# power_divider.net
KiCad netlist of a schematic drawn in EAGLE
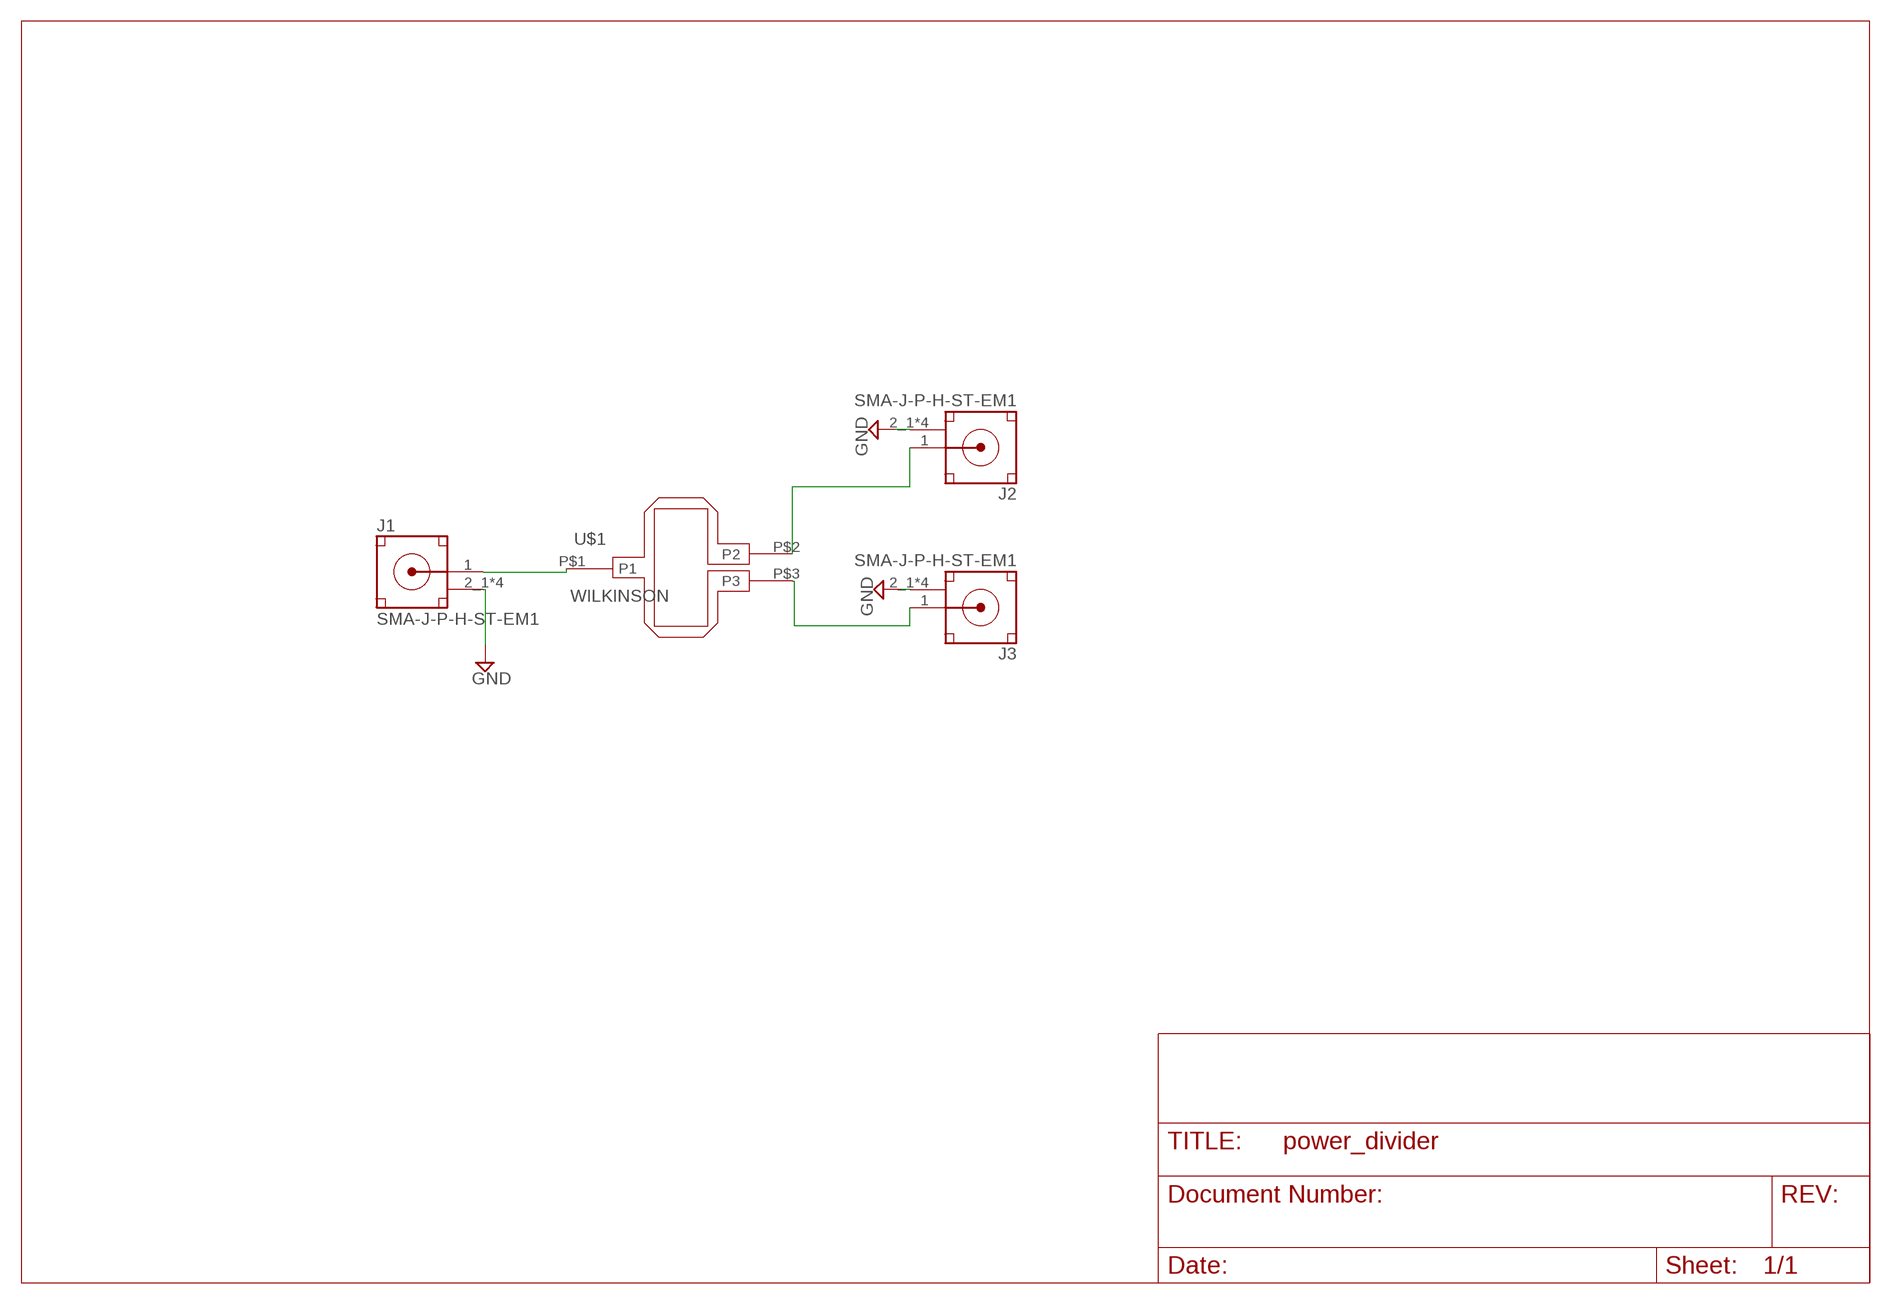
[diagram p0: schematic, sheet 1]

(export (version "E")
  (design (tool "Eeschema 10.0.6"))
  (components
    (comp (ref "J1")
      (value "SMA-J-P-H-ST-EM1")
      (footprint "eagle-import:SMA-J-P-H-ST-EM1")
      (fields (field (name "DIGI-KEY_PART_NUMBER") "SAM8857-ND") (field (name "MF") "Samtec"))
      (libsource (lib "eagle-import") (part "SMA-J-P-H-ST-EM1"))
    )
    (comp (ref "J2")
      (value "SMA-J-P-H-ST-EM1")
      (footprint "eagle-import:SMA-J-P-H-ST-EM1")
      (fields (field (name "DIGI-KEY_PART_NUMBER") "SAM8857-ND") (field (name "MF") "Samtec"))
      (libsource (lib "eagle-import") (part "SMA-J-P-H-ST-EM1"))
    )
    (comp (ref "J3")
      (value "SMA-J-P-H-ST-EM1")
      (footprint "eagle-import:SMA-J-P-H-ST-EM1")
      (fields (field (name "DIGI-KEY_PART_NUMBER") "SAM8857-ND") (field (name "MF") "Samtec"))
      (libsource (lib "eagle-import") (part "SMA-J-P-H-ST-EM1"))
    )
    (comp (ref "U$1")
      (value "WILKINSON")
      (footprint "eagle-import:WILKINSON")
      (libsource (lib "eagle-import") (part "WILKINSON"))
    )
  )
  (nets
    (net (code "1") (name "GND") (class "Default")
      (node (ref "J1") (pin "2_1") (pinfunction "GND_2_1") (pintype "power_in"))
      (node (ref "J1") (pin "2_2") (pinfunction "GND_2_2") (pintype "power_in"))
      (node (ref "J1") (pin "3_1") (pinfunction "GND_3_1") (pintype "power_in"))
      (node (ref "J1") (pin "3_2") (pinfunction "GND_3_2") (pintype "power_in"))
      (node (ref "J2") (pin "2_1") (pinfunction "GND_2_1") (pintype "power_in"))
      (node (ref "J2") (pin "2_2") (pinfunction "GND_2_2") (pintype "power_in"))
      (node (ref "J2") (pin "3_1") (pinfunction "GND_3_1") (pintype "power_in"))
      (node (ref "J2") (pin "3_2") (pinfunction "GND_3_2") (pintype "power_in"))
      (node (ref "J3") (pin "2_1") (pinfunction "GND_2_1") (pintype "power_in"))
      (node (ref "J3") (pin "2_2") (pinfunction "GND_2_2") (pintype "power_in"))
      (node (ref "J3") (pin "3_1") (pinfunction "GND_3_1") (pintype "power_in"))
      (node (ref "J3") (pin "3_2") (pinfunction "GND_3_2") (pintype "power_in"))
    )
    (net (code "2") (name "Net-(J1-SIGNAL)") (class "Default")
      (node (ref "J1") (pin "1") (pinfunction "SIGNAL_1") (pintype "passive"))
      (node (ref "U$1") (pin "P$1") (pinfunction "P1_P$1") (pintype "bidirectional"))
    )
    (net (code "3") (name "Net-(J2-SIGNAL)") (class "Default")
      (node (ref "J2") (pin "1") (pinfunction "SIGNAL_1") (pintype "passive"))
      (node (ref "U$1") (pin "P$2") (pinfunction "P2_P$2") (pintype "bidirectional"))
    )
    (net (code "4") (name "Net-(J3-SIGNAL)") (class "Default")
      (node (ref "J3") (pin "1") (pinfunction "SIGNAL_1") (pintype "passive"))
      (node (ref "U$1") (pin "P$3") (pinfunction "P3_P$3") (pintype "bidirectional"))
    )
  )
)
